# BatteryBaseBoard.net
KiCad netlist of a schematic drawn in Altium Designer
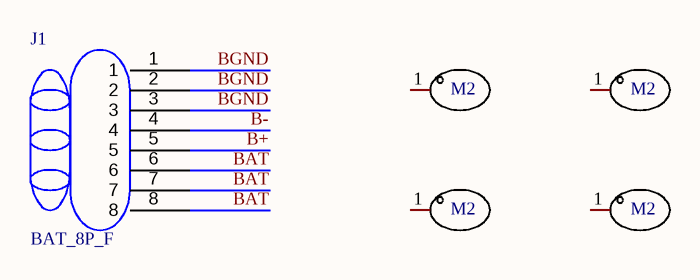
[diagram p0: BatteryBaseBoard.SchDoc]

(export (version "E")
  (design (tool "Eeschema 10.0.6"))
  (components
    (comp (ref "J1") (value "BAT_8P_F") (footprint "BAT_8P_F") (libsource (lib "BAT") (part "BAT_8P_F")))
    (comp (ref "U1")
      (value "SMTSO2020CTJ")
      (footprint "M2*4*1.5+2.5*1")
      (fields (field (name "MANUFACTURER") "Sinhoo(雄和远景)"))
      (libsource (lib "NUT-SMD") (part "M2_NUT"))
    )
    (comp (ref "U2")
      (value "SMTSO2020CTJ")
      (footprint "M2*4*1.5+2.5*1")
      (fields (field (name "MANUFACTURER") "Sinhoo(雄和远景)"))
      (libsource (lib "NUT-SMD") (part "M2_NUT"))
    )
    (comp (ref "U3")
      (value "SMTSO2020CTJ")
      (footprint "M2*4*1.5+2.5*1")
      (fields (field (name "MANUFACTURER") "Sinhoo(雄和远景)"))
      (libsource (lib "NUT-SMD") (part "M2_NUT"))
    )
    (comp (ref "U4")
      (value "SMTSO2020CTJ")
      (footprint "M2*4*1.5+2.5*1")
      (fields (field (name "MANUFACTURER") "Sinhoo(雄和远景)"))
      (libsource (lib "NUT-SMD") (part "M2_NUT"))
    )
  )
  (nets
    (net (code "1") (name "/B+") (class "Default")
      (node (ref "J1") (pin "5") (pinfunction "5_5") (pintype "passive"))
    )
    (net (code "2") (name "/B-") (class "Default")
      (node (ref "J1") (pin "4") (pinfunction "4_4") (pintype "passive"))
    )
    (net (code "3") (name "/BAT") (class "Default")
      (node (ref "J1") (pin "6") (pinfunction "6_6") (pintype "passive"))
      (node (ref "J1") (pin "7") (pinfunction "7_7") (pintype "passive"))
      (node (ref "J1") (pin "8") (pinfunction "8_8") (pintype "passive"))
    )
    (net (code "4") (name "/BGND") (class "Default")
      (node (ref "J1") (pin "1") (pinfunction "1_1") (pintype "passive"))
      (node (ref "J1") (pin "2") (pinfunction "2_2") (pintype "passive"))
      (node (ref "J1") (pin "3") (pinfunction "3_3") (pintype "passive"))
    )
    (net (code "5") (name "unconnected-(U1-Pad1)") (class "Default")
      (node (ref "U1") (pin "1") (pinfunction "1_1") (pintype "passive"))
    )
    (net (code "6") (name "unconnected-(U2-Pad1)") (class "Default")
      (node (ref "U2") (pin "1") (pinfunction "1_1") (pintype "passive"))
    )
    (net (code "7") (name "unconnected-(U3-Pad1)") (class "Default")
      (node (ref "U3") (pin "1") (pinfunction "1_1") (pintype "passive"))
    )
    (net (code "8") (name "unconnected-(U4-Pad1)") (class "Default")
      (node (ref "U4") (pin "1") (pinfunction "1_1") (pintype "passive"))
    )
  )
)
